# MCU.net
KiCad netlist of a schematic drawn in Altium Designer
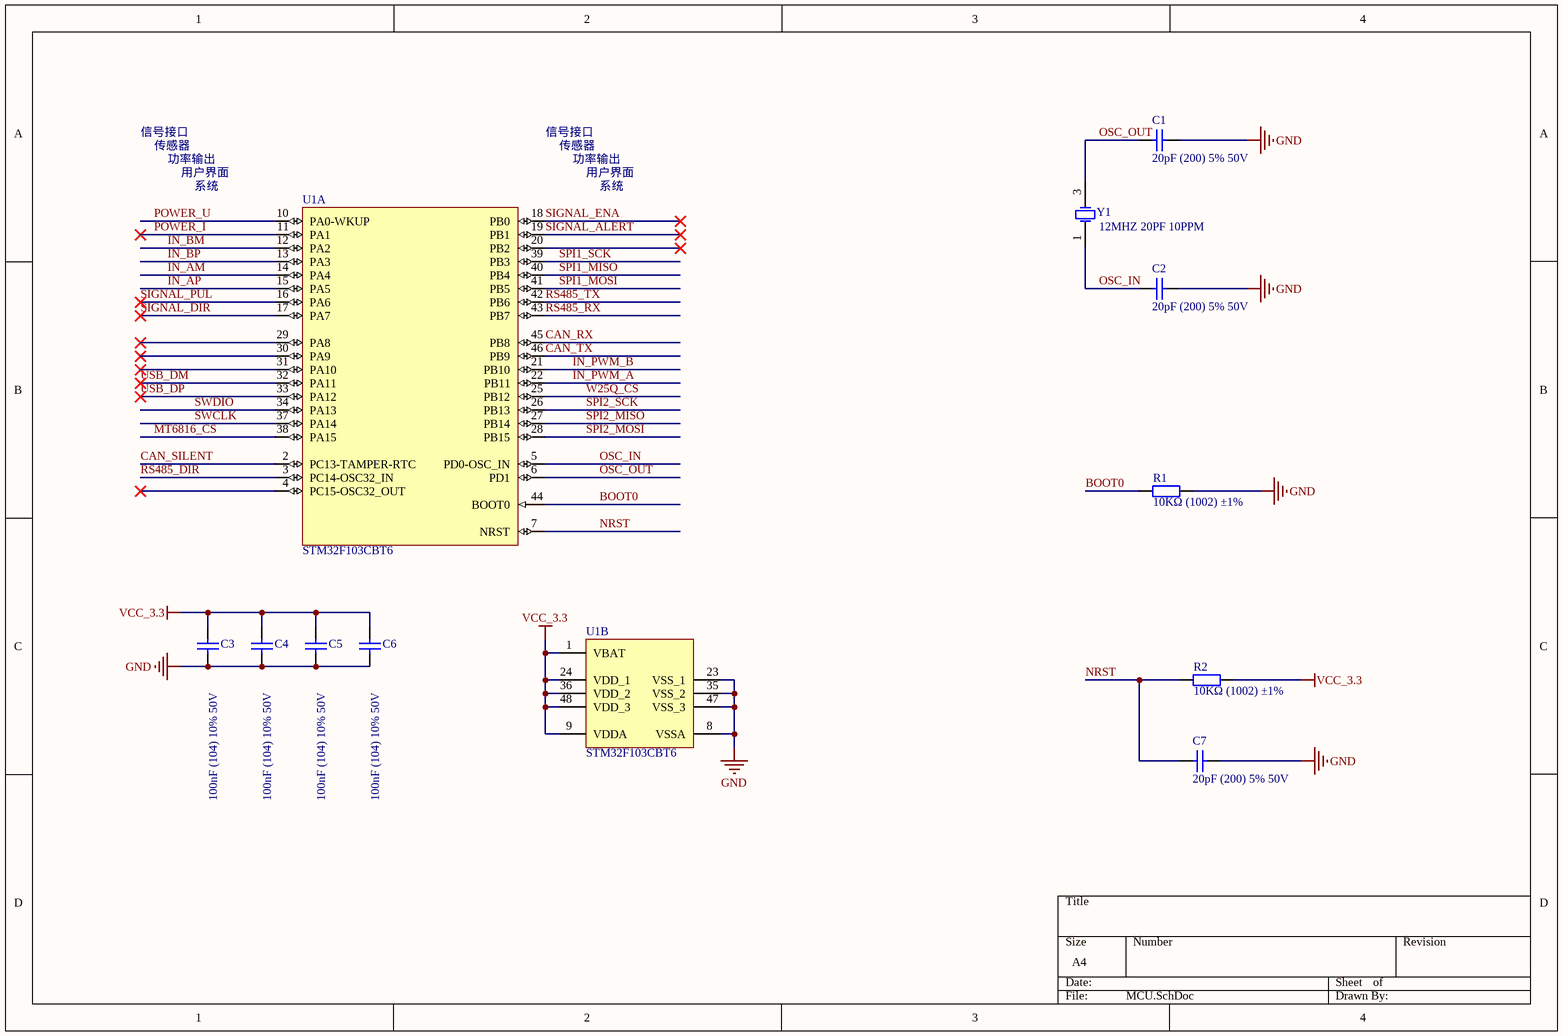
[diagram p0: MCU.SchDoc]

(export (version "E")
  (design (tool "Eeschema 10.0.6"))
  (components
    (comp (ref "C1")
      (value "20pF (200) 5% 50V")
      (footprint "0603_C")
      (description "贴片电容")
      (libsource (lib "X_Drive") (part "0603 20pF (200) 5% 50V"))
    )
    (comp (ref "C2")
      (value "20pF (200) 5% 50V")
      (footprint "0603_C")
      (description "贴片电容")
      (libsource (lib "X_Drive") (part "0603 20pF (200) 5% 50V"))
    )
    (comp (ref "C3")
      (value "100nF (104) 10% 50V")
      (footprint "0603_C")
      (description "贴片电容")
      (libsource (lib "X_Drive") (part "0603 100nF (104) 10% 50V"))
    )
    (comp (ref "C4")
      (value "100nF (104) 10% 50V")
      (footprint "0603_C")
      (description "贴片电容")
      (libsource (lib "X_Drive") (part "0603 100nF (104) 10% 50V"))
    )
    (comp (ref "C5")
      (value "100nF (104) 10% 50V")
      (footprint "0603_C")
      (description "贴片电容")
      (libsource (lib "X_Drive") (part "0603 100nF (104) 10% 50V"))
    )
    (comp (ref "C6")
      (value "100nF (104) 10% 50V")
      (footprint "0603_C")
      (description "贴片电容")
      (libsource (lib "X_Drive") (part "0603 100nF (104) 10% 50V"))
    )
    (comp (ref "C7")
      (value "20pF (200) 5% 50V")
      (footprint "0603_C")
      (description "贴片电容")
      (libsource (lib "X_Drive") (part "0603 20pF (200) 5% 50V"))
    )
    (comp (ref "R1")
      (value "10KΩ (1002) ±1%")
      (footprint "0603_R")
      (description "贴片电阻")
      (libsource (lib "X_Drive") (part "0603 10KΩ (1002) 1%"))
    )
    (comp (ref "R2")
      (value "10KΩ (1002) ±1%")
      (footprint "0603_R")
      (description "贴片电阻")
      (libsource (lib "X_Drive") (part "0603 10KΩ (1002) 1%"))
    )
    (comp (ref "U1")
      (value "STM32F103CBT6")
      (footprint "LQFP48_N")
      (libsource (lib "X_Drive") (part "STM32F103CBT6"))
    )
    (comp (ref "Y1")
      (value "12MHZ 20PF 10PPM")
      (footprint "SMD-3225_4P")
      (description "贴片晶振")
      (libsource (lib "X_Drive") (part "SMD-3225_4P  12MHZ 20PF 10PPM"))
    )
  )
  (nets
    (net (code "1") (name "/BOOT0") (class "Default")
      (node (ref "R1") (pin "1") (pinfunction "1_1") (pintype "passive"))
      (node (ref "U1") (pin "44") (pinfunction "BOOT0_44") (pintype "input"))
    )
    (net (code "2") (name "/CAN_RX") (class "Default")
      (node (ref "U1") (pin "45") (pinfunction "PB8_45") (pintype "bidirectional"))
    )
    (net (code "3") (name "/CAN_SILENT") (class "Default")
      (node (ref "U1") (pin "2") (pinfunction "PC13-TAMPER-RTC_2") (pintype "bidirectional"))
    )
    (net (code "4") (name "/CAN_TX") (class "Default")
      (node (ref "U1") (pin "46") (pinfunction "PB9_46") (pintype "bidirectional"))
    )
    (net (code "5") (name "/IN_AM") (class "Default")
      (node (ref "U1") (pin "14") (pinfunction "PA4_14") (pintype "bidirectional"))
    )
    (net (code "6") (name "/IN_AP") (class "Default")
      (node (ref "U1") (pin "15") (pinfunction "PA5_15") (pintype "bidirectional"))
    )
    (net (code "7") (name "/IN_BM") (class "Default")
      (node (ref "U1") (pin "12") (pinfunction "PA2_12") (pintype "bidirectional"))
    )
    (net (code "8") (name "/IN_BP") (class "Default")
      (node (ref "U1") (pin "13") (pinfunction "PA3_13") (pintype "bidirectional"))
    )
    (net (code "9") (name "/IN_PWM_A") (class "Default")
      (node (ref "U1") (pin "22") (pinfunction "PB11_22") (pintype "bidirectional"))
    )
    (net (code "10") (name "/IN_PWM_B") (class "Default")
      (node (ref "U1") (pin "21") (pinfunction "PB10_21") (pintype "bidirectional"))
    )
    (net (code "11") (name "/MT6816_CS") (class "Default")
      (node (ref "U1") (pin "38") (pinfunction "PA15_38") (pintype "bidirectional"))
    )
    (net (code "12") (name "/NRST") (class "Default")
      (node (ref "C7") (pin "1") (pinfunction "1_1") (pintype "passive"))
      (node (ref "R2") (pin "1") (pinfunction "1_1") (pintype "passive"))
      (node (ref "U1") (pin "7") (pinfunction "NRST_7") (pintype "bidirectional"))
    )
    (net (code "13") (name "/OSC_IN") (class "Default")
      (node (ref "C2") (pin "1") (pinfunction "1_1") (pintype "passive"))
      (node (ref "U1") (pin "5") (pinfunction "PD0-OSC_IN_5") (pintype "bidirectional"))
      (node (ref "Y1") (pin "1") (pinfunction "OSC1_1") (pintype "passive"))
    )
    (net (code "14") (name "/OSC_OUT") (class "Default")
      (node (ref "C1") (pin "1") (pinfunction "1_1") (pintype "passive"))
      (node (ref "U1") (pin "6") (pinfunction "PD1_6") (pintype "bidirectional"))
      (node (ref "Y1") (pin "3") (pinfunction "OSC2_3") (pintype "passive"))
    )
    (net (code "15") (name "/POWER_I") (class "Default")
      (node (ref "U1") (pin "11") (pinfunction "PA1_11") (pintype "bidirectional+no_connect"))
    )
    (net (code "16") (name "/POWER_U") (class "Default")
      (node (ref "U1") (pin "10") (pinfunction "PA0-WKUP_10") (pintype "bidirectional"))
    )
    (net (code "17") (name "/RS485_DIR") (class "Default")
      (node (ref "U1") (pin "3") (pinfunction "PC14-OSC32_IN_3") (pintype "bidirectional"))
    )
    (net (code "18") (name "/RS485_RX") (class "Default")
      (node (ref "U1") (pin "43") (pinfunction "PB7_43") (pintype "bidirectional"))
    )
    (net (code "19") (name "/RS485_TX") (class "Default")
      (node (ref "U1") (pin "42") (pinfunction "PB6_42") (pintype "bidirectional"))
    )
    (net (code "20") (name "/SIGNAL_ALERT") (class "Default")
      (node (ref "U1") (pin "19") (pinfunction "PB1_19") (pintype "bidirectional+no_connect"))
    )
    (net (code "21") (name "/SIGNAL_DIR") (class "Default")
      (node (ref "U1") (pin "17") (pinfunction "PA7_17") (pintype "bidirectional+no_connect"))
    )
    (net (code "22") (name "/SIGNAL_ENA") (class "Default")
      (node (ref "U1") (pin "18") (pinfunction "PB0_18") (pintype "bidirectional+no_connect"))
    )
    (net (code "23") (name "/SIGNAL_PUL") (class "Default")
      (node (ref "U1") (pin "16") (pinfunction "PA6_16") (pintype "bidirectional+no_connect"))
    )
    (net (code "24") (name "/SPI1_MISO") (class "Default")
      (node (ref "U1") (pin "40") (pinfunction "PB4_40") (pintype "bidirectional"))
    )
    (net (code "25") (name "/SPI1_MOSI") (class "Default")
      (node (ref "U1") (pin "41") (pinfunction "PB5_41") (pintype "bidirectional"))
    )
    (net (code "26") (name "/SPI1_SCK") (class "Default")
      (node (ref "U1") (pin "39") (pinfunction "PB3_39") (pintype "bidirectional"))
    )
    (net (code "27") (name "/SPI2_MISO") (class "Default")
      (node (ref "U1") (pin "27") (pinfunction "PB14_27") (pintype "bidirectional"))
    )
    (net (code "28") (name "/SPI2_MOSI") (class "Default")
      (node (ref "U1") (pin "28") (pinfunction "PB15_28") (pintype "bidirectional"))
    )
    (net (code "29") (name "/SPI2_SCK") (class "Default")
      (node (ref "U1") (pin "26") (pinfunction "PB13_26") (pintype "bidirectional"))
    )
    (net (code "30") (name "/SWCLK") (class "Default")
      (node (ref "U1") (pin "37") (pinfunction "PA14_37") (pintype "bidirectional"))
    )
    (net (code "31") (name "/SWDIO") (class "Default")
      (node (ref "U1") (pin "34") (pinfunction "PA13_34") (pintype "bidirectional"))
    )
    (net (code "32") (name "/USB_DM") (class "Default")
      (node (ref "U1") (pin "32") (pinfunction "PA11_32") (pintype "bidirectional+no_connect"))
    )
    (net (code "33") (name "/USB_DP") (class "Default")
      (node (ref "U1") (pin "33") (pinfunction "PA12_33") (pintype "bidirectional+no_connect"))
    )
    (net (code "34") (name "/W25Q_CS") (class "Default")
      (node (ref "U1") (pin "25") (pinfunction "PB12_25") (pintype "bidirectional"))
    )
    (net (code "35") (name "GND") (class "Default")
      (node (ref "C1") (pin "2") (pinfunction "2_2") (pintype "passive"))
      (node (ref "C2") (pin "2") (pinfunction "2_2") (pintype "passive"))
      (node (ref "C3") (pin "1") (pinfunction "1_1") (pintype "passive"))
      (node (ref "C4") (pin "1") (pinfunction "1_1") (pintype "passive"))
      (node (ref "C5") (pin "1") (pinfunction "1_1") (pintype "passive"))
      (node (ref "C6") (pin "1") (pinfunction "1_1") (pintype "passive"))
      (node (ref "C7") (pin "2") (pinfunction "2_2") (pintype "passive"))
      (node (ref "R1") (pin "2") (pinfunction "2_2") (pintype "passive"))
      (node (ref "U1") (pin "23") (pinfunction "VSS_1_23") (pintype "power_in"))
      (node (ref "U1") (pin "35") (pinfunction "VSS_2_35") (pintype "power_in"))
      (node (ref "U1") (pin "47") (pinfunction "VSS_3_47") (pintype "power_in"))
      (node (ref "U1") (pin "8") (pinfunction "VSSA_8") (pintype "power_in"))
    )
    (net (code "36") (name "VCC_3.3") (class "Default")
      (node (ref "C3") (pin "2") (pinfunction "2_2") (pintype "passive"))
      (node (ref "C4") (pin "2") (pinfunction "2_2") (pintype "passive"))
      (node (ref "C5") (pin "2") (pinfunction "2_2") (pintype "passive"))
      (node (ref "C6") (pin "2") (pinfunction "2_2") (pintype "passive"))
      (node (ref "R2") (pin "2") (pinfunction "2_2") (pintype "passive"))
      (node (ref "U1") (pin "1") (pinfunction "VBAT_1") (pintype "power_in"))
      (node (ref "U1") (pin "24") (pinfunction "VDD_1_24") (pintype "power_in"))
      (node (ref "U1") (pin "36") (pinfunction "VDD_2_36") (pintype "power_in"))
      (node (ref "U1") (pin "48") (pinfunction "VDD_3_48") (pintype "power_in"))
      (node (ref "U1") (pin "9") (pinfunction "VDDA_9") (pintype "power_in"))
    )
    (net (code "37") (name "unconnected-(U1A-PA8-Pad29)") (class "Default")
      (node (ref "U1") (pin "29") (pinfunction "PA8_29") (pintype "bidirectional+no_connect"))
    )
    (net (code "38") (name "unconnected-(U1A-PA9-Pad30)") (class "Default")
      (node (ref "U1") (pin "30") (pinfunction "PA9_30") (pintype "bidirectional+no_connect"))
    )
    (net (code "39") (name "unconnected-(U1A-PA10-Pad31)") (class "Default")
      (node (ref "U1") (pin "31") (pinfunction "PA10_31") (pintype "bidirectional+no_connect"))
    )
    (net (code "40") (name "unconnected-(U1A-PB2-Pad20)") (class "Default")
      (node (ref "U1") (pin "20") (pinfunction "PB2_20") (pintype "bidirectional+no_connect"))
    )
    (net (code "41") (name "unconnected-(U1A-PC15-OSC32_OUT-Pad4)") (class "Default")
      (node (ref "U1") (pin "4") (pinfunction "PC15-OSC32_OUT_4") (pintype "bidirectional+no_connect"))
    )
  )
)
